# Sheet1.net
KiCad netlist of a schematic drawn in Altium Designer
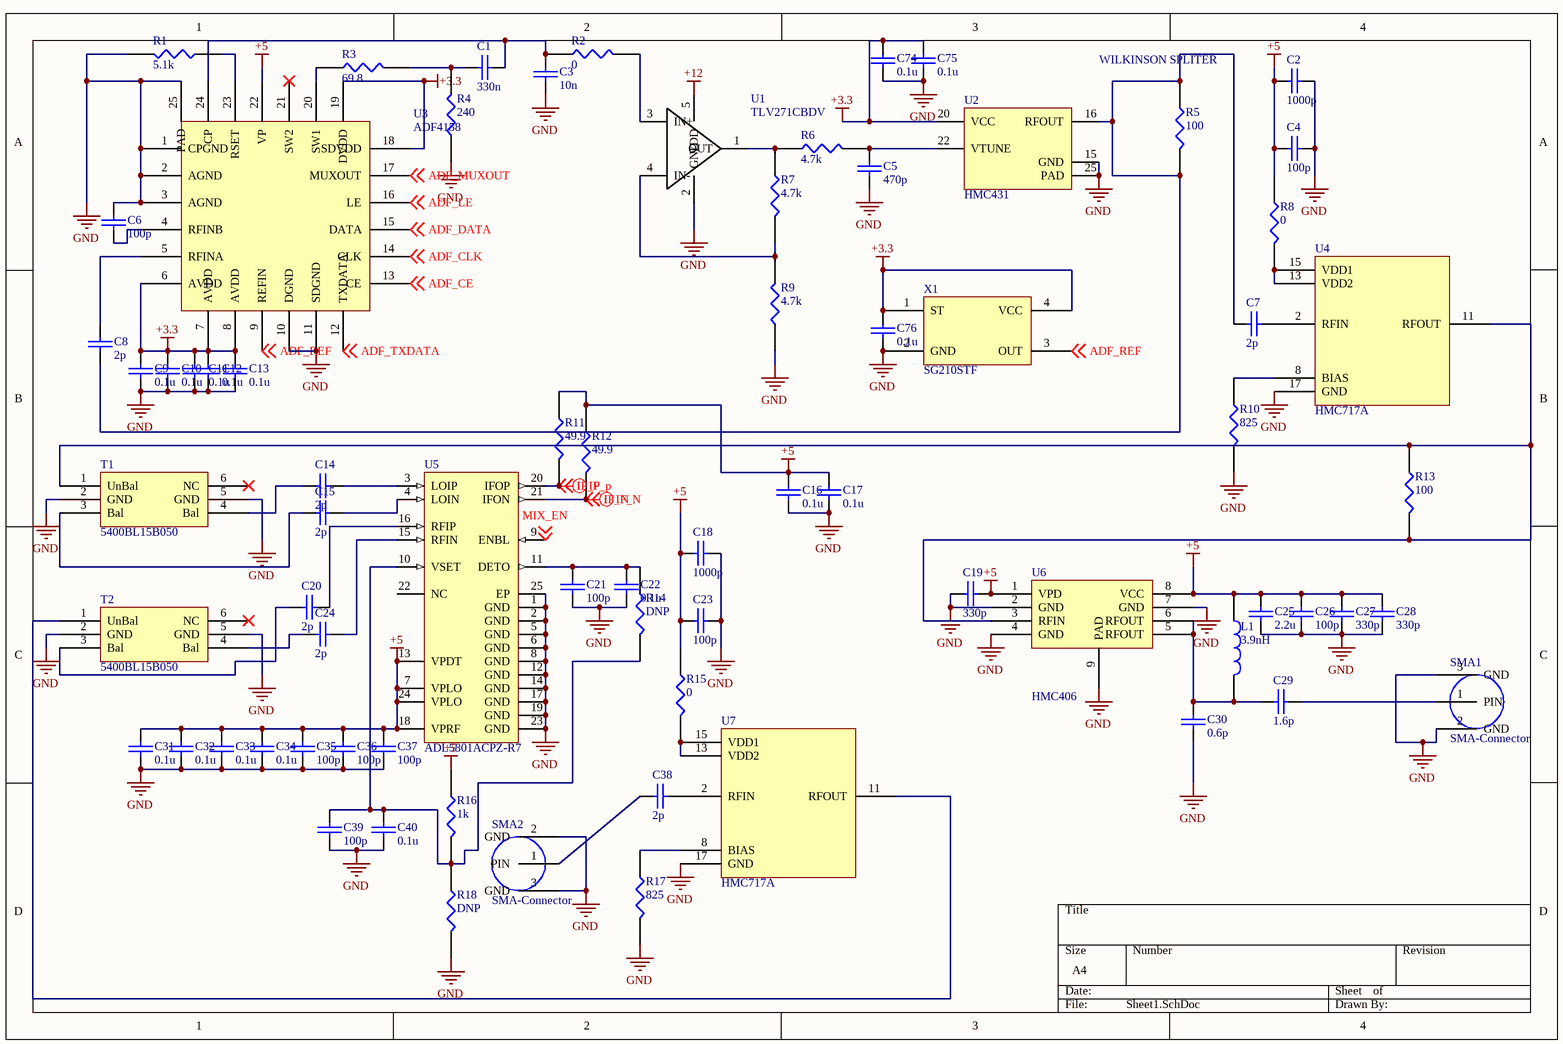
[diagram p0: Sheet1.SchDoc]

(export (version "E")
  (design (tool "Eeschema 10.0.6"))
  (components
    (comp (ref "C1")
      (value "330n")
      (footprint "0603_R")
      (description "Capacitor")
      (libsource (lib "Miscellaneous Devices") (part "CAP"))
    )
    (comp (ref "C2")
      (value "1000p")
      (footprint "0603_R")
      (description "Capacitor")
      (libsource (lib "Miscellaneous Devices") (part "CAP"))
    )
    (comp (ref "C3")
      (value "10n")
      (footprint "0603_R")
      (description "Capacitor")
      (libsource (lib "Miscellaneous Devices") (part "CAP"))
    )
    (comp (ref "C4")
      (value "100p")
      (footprint "0603_R")
      (description "Capacitor")
      (libsource (lib "Miscellaneous Devices") (part "CAP"))
    )
    (comp (ref "C5")
      (value "470p")
      (footprint "0603_R")
      (description "Capacitor")
      (libsource (lib "Miscellaneous Devices") (part "CAP"))
    )
    (comp (ref "C6")
      (value "100p")
      (footprint "0603_R")
      (description "Capacitor")
      (libsource (lib "Miscellaneous Devices") (part "CAP"))
    )
    (comp (ref "C7")
      (value "2p")
      (footprint "0603_R")
      (description "Capacitor")
      (libsource (lib "Miscellaneous Devices") (part "CAP"))
    )
    (comp (ref "C8")
      (value "2p")
      (footprint "0603_R")
      (description "Capacitor")
      (libsource (lib "Miscellaneous Devices") (part "CAP"))
    )
    (comp (ref "C9")
      (value "0.1u")
      (footprint "0603_R")
      (description "Capacitor")
      (libsource (lib "Miscellaneous Devices") (part "CAP"))
    )
    (comp (ref "C10")
      (value "0.1u")
      (footprint "0603_R")
      (description "Capacitor")
      (libsource (lib "Miscellaneous Devices") (part "CAP"))
    )
    (comp (ref "C11")
      (value "0.1u")
      (footprint "0603_R")
      (description "Capacitor")
      (libsource (lib "Miscellaneous Devices") (part "CAP"))
    )
    (comp (ref "C12")
      (value "0.1u")
      (footprint "0603_R")
      (description "Capacitor")
      (libsource (lib "Miscellaneous Devices") (part "CAP"))
    )
    (comp (ref "C13")
      (value "0.1u")
      (footprint "0603_R")
      (description "Capacitor")
      (libsource (lib "Miscellaneous Devices") (part "CAP"))
    )
    (comp (ref "C14")
      (value "2p")
      (footprint "0603_R")
      (description "Capacitor")
      (libsource (lib "Miscellaneous Devices") (part "CAP"))
    )
    (comp (ref "C15")
      (value "2p")
      (footprint "0603_R")
      (description "Capacitor")
      (libsource (lib "Miscellaneous Devices") (part "CAP"))
    )
    (comp (ref "C16")
      (value "0.1u")
      (footprint "0603_R")
      (description "Capacitor")
      (libsource (lib "Miscellaneous Devices") (part "CAP"))
    )
    (comp (ref "C17")
      (value "0.1u")
      (footprint "0603_R")
      (description "Capacitor")
      (libsource (lib "Miscellaneous Devices") (part "CAP"))
    )
    (comp (ref "C18")
      (value "1000p")
      (footprint "0603_R")
      (description "Capacitor")
      (libsource (lib "Miscellaneous Devices") (part "CAP"))
    )
    (comp (ref "C19")
      (value "330p")
      (footprint "0603_R")
      (description "Capacitor")
      (libsource (lib "Miscellaneous Devices") (part "CAP"))
    )
    (comp (ref "C20")
      (value "2p")
      (footprint "0603_R")
      (description "Capacitor")
      (libsource (lib "Miscellaneous Devices") (part "CAP"))
    )
    (comp (ref "C21")
      (value "100p")
      (footprint "0603_R")
      (description "Capacitor")
      (libsource (lib "Miscellaneous Devices") (part "CAP"))
    )
    (comp (ref "C22")
      (value "0.1u")
      (footprint "0603_R")
      (description "Capacitor")
      (libsource (lib "Miscellaneous Devices") (part "CAP"))
    )
    (comp (ref "C23")
      (value "100p")
      (footprint "0603_R")
      (description "Capacitor")
      (libsource (lib "Miscellaneous Devices") (part "CAP"))
    )
    (comp (ref "C24")
      (value "2p")
      (footprint "0603_R")
      (description "Capacitor")
      (libsource (lib "Miscellaneous Devices") (part "CAP"))
    )
    (comp (ref "C25")
      (value "2.2u")
      (footprint "0603_R")
      (description "Capacitor")
      (libsource (lib "Miscellaneous Devices") (part "CAP"))
    )
    (comp (ref "C26")
      (value "100p")
      (footprint "0603_R")
      (description "Capacitor")
      (libsource (lib "Miscellaneous Devices") (part "CAP"))
    )
    (comp (ref "C27")
      (value "330p")
      (footprint "0603_R")
      (description "Capacitor")
      (libsource (lib "Miscellaneous Devices") (part "CAP"))
    )
    (comp (ref "C28")
      (value "330p")
      (footprint "0603_R")
      (description "Capacitor")
      (libsource (lib "Miscellaneous Devices") (part "CAP"))
    )
    (comp (ref "C29")
      (value "1.6p")
      (footprint "0603_R")
      (description "Capacitor")
      (libsource (lib "Miscellaneous Devices") (part "CAP"))
    )
    (comp (ref "C30")
      (value "0.6p")
      (footprint "0603_R")
      (description "Capacitor")
      (libsource (lib "Miscellaneous Devices") (part "CAP"))
    )
    (comp (ref "C31")
      (value "0.1u")
      (footprint "0603_R")
      (description "Capacitor")
      (libsource (lib "Miscellaneous Devices") (part "CAP"))
    )
    (comp (ref "C32")
      (value "0.1u")
      (footprint "0603_R")
      (description "Capacitor")
      (libsource (lib "Miscellaneous Devices") (part "CAP"))
    )
    (comp (ref "C33")
      (value "0.1u")
      (footprint "0603_R")
      (description "Capacitor")
      (libsource (lib "Miscellaneous Devices") (part "CAP"))
    )
    (comp (ref "C34")
      (value "0.1u")
      (footprint "0603_R")
      (description "Capacitor")
      (libsource (lib "Miscellaneous Devices") (part "CAP"))
    )
    (comp (ref "C35")
      (value "100p")
      (footprint "0603_R")
      (description "Capacitor")
      (libsource (lib "Miscellaneous Devices") (part "CAP"))
    )
    (comp (ref "C36")
      (value "100p")
      (footprint "0603_R")
      (description "Capacitor")
      (libsource (lib "Miscellaneous Devices") (part "CAP"))
    )
    (comp (ref "C37")
      (value "100p")
      (footprint "0603_R")
      (description "Capacitor")
      (libsource (lib "Miscellaneous Devices") (part "CAP"))
    )
    (comp (ref "C38")
      (value "2p")
      (footprint "0603_R")
      (description "Capacitor")
      (libsource (lib "Miscellaneous Devices") (part "CAP"))
    )
    (comp (ref "C39")
      (value "100p")
      (footprint "0603_R")
      (description "Capacitor")
      (libsource (lib "Miscellaneous Devices") (part "CAP"))
    )
    (comp (ref "C40")
      (value "0.1u")
      (footprint "0603_R")
      (description "Capacitor")
      (libsource (lib "Miscellaneous Devices") (part "CAP"))
    )
    (comp (ref "C74")
      (value "0.1u")
      (footprint "0603_R")
      (description "Capacitor")
      (libsource (lib "Miscellaneous Devices") (part "CAP"))
    )
    (comp (ref "C75")
      (value "0.1u")
      (footprint "0603_R")
      (description "Capacitor")
      (libsource (lib "Miscellaneous Devices") (part "CAP"))
    )
    (comp (ref "C76")
      (value "0.1u")
      (footprint "0603_R")
      (description "Capacitor")
      (libsource (lib "Miscellaneous Devices") (part "CAP"))
    )
    (comp (ref "L1")
      (value "3.9nH")
      (footprint "0603_R")
      (libsource (lib "Miscellaneous Devices") (part "INDUCTOR"))
    )
    (comp (ref "R1")
      (value "5.1k")
      (footprint "0603_R")
      (libsource (lib "Miscellaneous Devices") (part "RES1"))
    )
    (comp (ref "R2") (value "0") (footprint "0603_R") (libsource (lib "Miscellaneous Devices") (part "RES1")))
    (comp (ref "R3")
      (value "69.8")
      (footprint "0603_R")
      (libsource (lib "Miscellaneous Devices") (part "RES1"))
    )
    (comp (ref "R4")
      (value "240")
      (footprint "0603_R")
      (libsource (lib "Miscellaneous Devices") (part "RES1"))
    )
    (comp (ref "R5")
      (value "100")
      (footprint "0603_R")
      (libsource (lib "Miscellaneous Devices") (part "RES1"))
    )
    (comp (ref "R6")
      (value "4.7k")
      (footprint "0603_R")
      (libsource (lib "Miscellaneous Devices") (part "RES1"))
    )
    (comp (ref "R7")
      (value "4.7k")
      (footprint "0603_R")
      (libsource (lib "Miscellaneous Devices") (part "RES1"))
    )
    (comp (ref "R8") (value "0") (footprint "0603_R") (libsource (lib "Miscellaneous Devices") (part "RES1")))
    (comp (ref "R9")
      (value "4.7k")
      (footprint "0603_R")
      (libsource (lib "Miscellaneous Devices") (part "RES1"))
    )
    (comp (ref "R10")
      (value "825")
      (footprint "0603_R")
      (libsource (lib "Miscellaneous Devices") (part "RES1"))
    )
    (comp (ref "R11")
      (value "49.9")
      (footprint "0603_R")
      (libsource (lib "Miscellaneous Devices") (part "RES1"))
    )
    (comp (ref "R12")
      (value "49.9")
      (footprint "0603_R")
      (libsource (lib "Miscellaneous Devices") (part "RES1"))
    )
    (comp (ref "R13")
      (value "100")
      (footprint "0603_R")
      (libsource (lib "Miscellaneous Devices") (part "RES1"))
    )
    (comp (ref "R14")
      (value "DNP")
      (footprint "0603_R")
      (libsource (lib "Miscellaneous Devices") (part "RES1"))
    )
    (comp (ref "R15")
      (value "0")
      (footprint "0603_R")
      (libsource (lib "Miscellaneous Devices") (part "RES1"))
    )
    (comp (ref "R16")
      (value "1k")
      (footprint "0603_R")
      (libsource (lib "Miscellaneous Devices") (part "RES1"))
    )
    (comp (ref "R17")
      (value "825")
      (footprint "0603_R")
      (libsource (lib "Miscellaneous Devices") (part "RES1"))
    )
    (comp (ref "R18")
      (value "DNP")
      (footprint "0603_R")
      (libsource (lib "Miscellaneous Devices") (part "RES1"))
    )
    (comp (ref "SMA1")
      (value "SMA-Connector")
      (footprint "SMA-2")
      (libsource (lib "SMA") (part "SMA-Connector"))
    )
    (comp (ref "SMA2")
      (value "SMA-Connector")
      (footprint "SMA-2")
      (libsource (lib "SMA") (part "SMA-Connector"))
    )
    (comp (ref "T1")
      (value "5400BL15B050")
      (footprint "0603-6")
      (libsource (lib "Proj") (part "5400BL15B050"))
    )
    (comp (ref "T2")
      (value "5400BL15B050")
      (footprint "0603-6")
      (libsource (lib "Proj") (part "5400BL15B050"))
    )
    (comp (ref "U1")
      (value "TLV271CBDV")
      (footprint "LT-S5-5-TSOT-23_L")
      (libsource (lib "Schlib1") (part "TLV271CBDV"))
    )
    (comp (ref "U2") (value "HMC431") (footprint "LCC24-HMC431") (libsource (lib "Schlib1") (part "HMC431")))
    (comp (ref "U3")
      (value "ADF4158")
      (footprint "LCC24_ADF4158")
      (libsource (lib "Schlib1") (part "ADF4518"))
    )
    (comp (ref "U4") (value "HMC717A") (footprint "LCC16-717A") (libsource (lib "Proj") (part "HMC717A")))
    (comp (ref "U5")
      (value "ADL5801ACPZ-R7")
      (footprint "ADI-CP-24-3_N")
      (description "High IP3, 10 MHz to 6 GHz, Active Mixer, 130mA Supply Current, CP-24-3, Pb-Free, 1500 Reel")
      (libsource (lib "Analog Devices RF IF Mixers and Multipliers") (part "ADL5801ACPZ-R7"))
    )
    (comp (ref "U6") (value "HMC406") (libsource (lib "Proj") (part "HMC406")))
    (comp (ref "U7") (value "HMC717A") (footprint "LCC16-717A") (libsource (lib "Proj") (part "HMC717A")))
    (comp (ref "X1") (value "SG210STF") (footprint "SG210STF") (libsource (lib "Proj") (part "SG210STF")))
  )
  (nets
    (net (code "1") (name "+3.3") (class "Default")
      (node (ref "C10") (pin "1") (pinfunction "1_1") (pintype "passive"))
      (node (ref "C11") (pin "1") (pinfunction "1_1") (pintype "passive"))
      (node (ref "C12") (pin "1") (pinfunction "1_1") (pintype "passive"))
      (node (ref "C13") (pin "1") (pinfunction "1_1") (pintype "passive"))
      (node (ref "C74") (pin "2") (pinfunction "2_2") (pintype "passive"))
      (node (ref "C75") (pin "2") (pinfunction "2_2") (pintype "passive"))
      (node (ref "C76") (pin "1") (pinfunction "1_1") (pintype "passive"))
      (node (ref "C9") (pin "1") (pinfunction "1_1") (pintype "passive"))
      (node (ref "U2") (pin "20") (pinfunction "VCC_20") (pintype "passive"))
      (node (ref "U3") (pin "18") (pinfunction "SDVDD_18") (pintype "passive"))
      (node (ref "U3") (pin "19") (pinfunction "DVDD_19") (pintype "passive"))
      (node (ref "U3") (pin "6") (pinfunction "AVDD_6") (pintype "passive"))
      (node (ref "U3") (pin "7") (pinfunction "AVDD_7") (pintype "passive"))
      (node (ref "U3") (pin "8") (pinfunction "AVDD_8") (pintype "passive"))
      (node (ref "X1") (pin "1") (pinfunction "ST_1") (pintype "passive"))
      (node (ref "X1") (pin "4") (pinfunction "VCC_4") (pintype "passive"))
    )
    (net (code "2") (name "+5") (class "Default")
      (node (ref "C16") (pin "2") (pinfunction "2_2") (pintype "passive"))
      (node (ref "C17") (pin "2") (pinfunction "2_2") (pintype "passive"))
      (node (ref "C18") (pin "1") (pinfunction "1_1") (pintype "passive"))
      (node (ref "C19") (pin "1") (pinfunction "1_1") (pintype "passive"))
      (node (ref "C2") (pin "1") (pinfunction "1_1") (pintype "passive"))
      (node (ref "C23") (pin "1") (pinfunction "1_1") (pintype "passive"))
      (node (ref "C25") (pin "2") (pinfunction "2_2") (pintype "passive"))
      (node (ref "C26") (pin "2") (pinfunction "2_2") (pintype "passive"))
      (node (ref "C27") (pin "2") (pinfunction "2_2") (pintype "passive"))
      (node (ref "C28") (pin "2") (pinfunction "2_2") (pintype "passive"))
      (node (ref "C31") (pin "2") (pinfunction "2_2") (pintype "passive"))
      (node (ref "C32") (pin "2") (pinfunction "2_2") (pintype "passive"))
      (node (ref "C33") (pin "2") (pinfunction "2_2") (pintype "passive"))
      (node (ref "C34") (pin "2") (pinfunction "2_2") (pintype "passive"))
      (node (ref "C35") (pin "2") (pinfunction "2_2") (pintype "passive"))
      (node (ref "C36") (pin "2") (pinfunction "2_2") (pintype "passive"))
      (node (ref "C37") (pin "2") (pinfunction "2_2") (pintype "passive"))
      (node (ref "C4") (pin "1") (pinfunction "1_1") (pintype "passive"))
      (node (ref "L1") (pin "1") (pinfunction "1_1") (pintype "passive"))
      (node (ref "R11") (pin "1") (pinfunction "1_1") (pintype "passive"))
      (node (ref "R12") (pin "1") (pinfunction "1_1") (pintype "passive"))
      (node (ref "R15") (pin "1") (pinfunction "1_1") (pintype "passive"))
      (node (ref "R16") (pin "1") (pinfunction "1_1") (pintype "passive"))
      (node (ref "R8") (pin "1") (pinfunction "1_1") (pintype "passive"))
      (node (ref "U3") (pin "22") (pinfunction "VP_22") (pintype "passive"))
      (node (ref "U5") (pin "13") (pinfunction "VPDT_13") (pintype "power_in"))
      (node (ref "U5") (pin "18") (pinfunction "VPRF_18") (pintype "power_in"))
      (node (ref "U5") (pin "24") (pinfunction "VPLO_24") (pintype "power_in"))
      (node (ref "U5") (pin "7") (pinfunction "VPLO_7") (pintype "power_in"))
      (node (ref "U6") (pin "1") (pinfunction "VPD_1") (pintype "passive"))
      (node (ref "U6") (pin "8") (pinfunction "VCC_8") (pintype "passive"))
    )
    (net (code "3") (name "+12") (class "Default")
      (node (ref "U1") (pin "5") (pinfunction "VDD_5") (pintype "passive"))
    )
    (net (code "4") (name "ADF_CE") (class "Default")
      (node (ref "U3") (pin "13") (pinfunction "CE_13") (pintype "passive"))
    )
    (net (code "5") (name "ADF_CLK") (class "Default")
      (node (ref "U3") (pin "14") (pinfunction "CLK_14") (pintype "passive"))
    )
    (net (code "6") (name "ADF_DATA") (class "Default")
      (node (ref "U3") (pin "15") (pinfunction "DATA_15") (pintype "passive"))
    )
    (net (code "7") (name "ADF_LE") (class "Default")
      (node (ref "U3") (pin "16") (pinfunction "LE_16") (pintype "passive"))
    )
    (net (code "8") (name "ADF_MUXOUT") (class "Default")
      (node (ref "U3") (pin "17") (pinfunction "MUXOUT_17") (pintype "passive"))
    )
    (net (code "9") (name "ADF_REF") (class "Default")
      (node (ref "U3") (pin "9") (pinfunction "REFIN_9") (pintype "passive"))
      (node (ref "X1") (pin "3") (pinfunction "OUT_3") (pintype "passive"))
    )
    (net (code "10") (name "ADF_TXDATA") (class "Default")
      (node (ref "U3") (pin "12") (pinfunction "TXDATA_12") (pintype "passive"))
    )
    (net (code "11") (name "GND") (class "Default")
      (node (ref "C10") (pin "2") (pinfunction "2_2") (pintype "passive"))
      (node (ref "C11") (pin "2") (pinfunction "2_2") (pintype "passive"))
      (node (ref "C12") (pin "2") (pinfunction "2_2") (pintype "passive"))
      (node (ref "C13") (pin "2") (pinfunction "2_2") (pintype "passive"))
      (node (ref "C16") (pin "1") (pinfunction "1_1") (pintype "passive"))
      (node (ref "C17") (pin "1") (pinfunction "1_1") (pintype "passive"))
      (node (ref "C18") (pin "2") (pinfunction "2_2") (pintype "passive"))
      (node (ref "C19") (pin "2") (pinfunction "2_2") (pintype "passive"))
      (node (ref "C2") (pin "2") (pinfunction "2_2") (pintype "passive"))
      (node (ref "C21") (pin "1") (pinfunction "1_1") (pintype "passive"))
      (node (ref "C22") (pin "1") (pinfunction "1_1") (pintype "passive"))
      (node (ref "C23") (pin "2") (pinfunction "2_2") (pintype "passive"))
      (node (ref "C25") (pin "1") (pinfunction "1_1") (pintype "passive"))
      (node (ref "C26") (pin "1") (pinfunction "1_1") (pintype "passive"))
      (node (ref "C27") (pin "1") (pinfunction "1_1") (pintype "passive"))
      (node (ref "C28") (pin "1") (pinfunction "1_1") (pintype "passive"))
      (node (ref "C3") (pin "2") (pinfunction "2_2") (pintype "passive"))
      (node (ref "C30") (pin "1") (pinfunction "1_1") (pintype "passive"))
      (node (ref "C31") (pin "1") (pinfunction "1_1") (pintype "passive"))
      (node (ref "C32") (pin "1") (pinfunction "1_1") (pintype "passive"))
      (node (ref "C33") (pin "1") (pinfunction "1_1") (pintype "passive"))
      (node (ref "C34") (pin "1") (pinfunction "1_1") (pintype "passive"))
      (node (ref "C35") (pin "1") (pinfunction "1_1") (pintype "passive"))
      (node (ref "C36") (pin "1") (pinfunction "1_1") (pintype "passive"))
      (node (ref "C37") (pin "1") (pinfunction "1_1") (pintype "passive"))
      (node (ref "C39") (pin "1") (pinfunction "1_1") (pintype "passive"))
      (node (ref "C4") (pin "2") (pinfunction "2_2") (pintype "passive"))
      (node (ref "C40") (pin "1") (pinfunction "1_1") (pintype "passive"))
      (node (ref "C5") (pin "2") (pinfunction "2_2") (pintype "passive"))
      (node (ref "C6") (pin "1") (pinfunction "1_1") (pintype "passive"))
      (node (ref "C74") (pin "1") (pinfunction "1_1") (pintype "passive"))
      (node (ref "C75") (pin "1") (pinfunction "1_1") (pintype "passive"))
      (node (ref "C76") (pin "2") (pinfunction "2_2") (pintype "passive"))
      (node (ref "C9") (pin "2") (pinfunction "2_2") (pintype "passive"))
      (node (ref "R1") (pin "2") (pinfunction "2_2") (pintype "passive"))
      (node (ref "R10") (pin "2") (pinfunction "2_2") (pintype "passive"))
      (node (ref "R17") (pin "2") (pinfunction "2_2") (pintype "passive"))
      (node (ref "R18") (pin "2") (pinfunction "2_2") (pintype "passive"))
      (node (ref "R4") (pin "1") (pinfunction "1_1") (pintype "passive"))
      (node (ref "R9") (pin "1") (pinfunction "1_1") (pintype "passive"))
      (node (ref "SMA1") (pin "2") (pinfunction "GND_2") (pintype "passive"))
      (node (ref "SMA1") (pin "3") (pinfunction "GND_3") (pintype "passive"))
      (node (ref "SMA2") (pin "2") (pinfunction "GND_2") (pintype "passive"))
      (node (ref "SMA2") (pin "3") (pinfunction "GND_3") (pintype "passive"))
      (node (ref "T1") (pin "2") (pinfunction "GND_2") (pintype "passive"))
      (node (ref "T1") (pin "5") (pinfunction "GND_5") (pintype "passive"))
      (node (ref "T2") (pin "2") (pinfunction "GND_2") (pintype "passive"))
      (node (ref "T2") (pin "5") (pinfunction "GND_5") (pintype "passive"))
      (node (ref "U1") (pin "2") (pinfunction "GND_2") (pintype "passive"))
      (node (ref "U2") (pin "15") (pinfunction "GND_15") (pintype "passive"))
      (node (ref "U2") (pin "25") (pinfunction "PAD_25") (pintype "passive"))
      (node (ref "U3") (pin "1") (pinfunction "CPGND_1") (pintype "passive"))
      (node (ref "U3") (pin "10") (pinfunction "DGND_10") (pintype "passive"))
      (node (ref "U3") (pin "11") (pinfunction "SDGND_11") (pintype "passive"))
      (node (ref "U3") (pin "2") (pinfunction "AGND_2") (pintype "passive"))
      (node (ref "U3") (pin "25") (pinfunction "PAD_25") (pintype "passive"))
      (node (ref "U3") (pin "3") (pinfunction "AGND_3") (pintype "passive"))
      (node (ref "U4") (pin "17") (pinfunction "GND_17") (pintype "passive"))
      (node (ref "U5") (pin "1") (pinfunction "GND_1") (pintype "power_in"))
      (node (ref "U5") (pin "12") (pinfunction "GND_12") (pintype "power_in"))
      (node (ref "U5") (pin "14") (pinfunction "GND_14") (pintype "power_in"))
      (node (ref "U5") (pin "17") (pinfunction "GND_17") (pintype "power_in"))
      (node (ref "U5") (pin "19") (pinfunction "GND_19") (pintype "power_in"))
      (node (ref "U5") (pin "2") (pinfunction "GND_2") (pintype "power_in"))
      (node (ref "U5") (pin "23") (pinfunction "GND_23") (pintype "power_in"))
      (node (ref "U5") (pin "25") (pinfunction "EP_25") (pintype "power_in"))
      (node (ref "U5") (pin "5") (pinfunction "GND_5") (pintype "power_in"))
      (node (ref "U5") (pin "6") (pinfunction "GND_6") (pintype "power_in"))
      (node (ref "U5") (pin "8") (pinfunction "GND_8") (pintype "power_in"))
      (node (ref "U6") (pin "2") (pinfunction "GND_2") (pintype "passive"))
      (node (ref "U6") (pin "4") (pinfunction "GND_4") (pintype "passive"))
      (node (ref "U6") (pin "7") (pinfunction "GND_7") (pintype "passive"))
      (node (ref "U6") (pin "9") (pinfunction "PAD_9") (pintype "passive"))
      (node (ref "U7") (pin "17") (pinfunction "GND_17") (pintype "passive"))
      (node (ref "X1") (pin "2") (pinfunction "GND_2") (pintype "passive"))
    )
    (net (code "12") (name "IF_N") (class "Default")
      (node (ref "R12") (pin "2") (pinfunction "2_2") (pintype "passive"))
      (node (ref "U5") (pin "21") (pinfunction "IFON_21") (pintype "output"))
    )
    (net (code "13") (name "IF_P") (class "Default")
      (node (ref "R11") (pin "2") (pinfunction "2_2") (pintype "passive"))
      (node (ref "U5") (pin "20") (pinfunction "IFOP_20") (pintype "output"))
    )
    (net (code "14") (name "MIX_EN") (class "Default")
      (node (ref "U5") (pin "9") (pinfunction "ENBL_9") (pintype "input"))
    )
    (net (code "15") (name "Net-(C1-Pad1)") (class "Default")
      (node (ref "C1") (pin "1") (pinfunction "1_1") (pintype "passive"))
      (node (ref "R3") (pin "2") (pinfunction "2_2") (pintype "passive"))
      (node (ref "R4") (pin "2") (pinfunction "2_2") (pintype "passive"))
    )
    (net (code "16") (name "Net-(C14-Pad1)") (class "Default")
      (node (ref "C14") (pin "1") (pinfunction "1_1") (pintype "passive"))
      (node (ref "T1") (pin "4") (pinfunction "Bal_4") (pintype "passive"))
    )
    (net (code "17") (name "Net-(C15-Pad1)") (class "Default")
      (node (ref "C15") (pin "1") (pinfunction "1_1") (pintype "passive"))
      (node (ref "T1") (pin "3") (pinfunction "Bal_3") (pintype "passive"))
    )
    (net (code "18") (name "Net-(C20-Pad1)") (class "Default")
      (node (ref "C20") (pin "1") (pinfunction "1_1") (pintype "passive"))
      (node (ref "T2") (pin "3") (pinfunction "Bal_3") (pintype "passive"))
    )
    (net (code "19") (name "Net-(C24-Pad1)") (class "Default")
      (node (ref "C24") (pin "1") (pinfunction "1_1") (pintype "passive"))
      (node (ref "T2") (pin "4") (pinfunction "Bal_4") (pintype "passive"))
    )
    (net (code "20") (name "Net-(C29-Pad2)") (class "Default")
      (node (ref "C29") (pin "2") (pinfunction "2_2") (pintype "passive"))
      (node (ref "C30") (pin "2") (pinfunction "2_2") (pintype "passive"))
      (node (ref "L1") (pin "2") (pinfunction "2_2") (pintype "passive"))
      (node (ref "U6") (pin "5") (pinfunction "RFOUT_5") (pintype "passive"))
      (node (ref "U6") (pin "6") (pinfunction "RFOUT_6") (pintype "passive"))
    )
    (net (code "21") (name "Net-(SMA1-PIN)") (class "Default")
      (node (ref "C29") (pin "1") (pinfunction "1_1") (pintype "passive"))
      (node (ref "SMA1") (pin "1") (pinfunction "PIN_1") (pintype "passive"))
    )
    (net (code "22") (name "Net-(SMA2-PIN)") (class "Default")
      (node (ref "C38") (pin "1") (pinfunction "1_1") (pintype "passive"))
      (node (ref "SMA2") (pin "1") (pinfunction "PIN_1") (pintype "passive"))
    )
    (net (code "23") (name "Net-(T1-UnBal)") (class "Default")
      (node (ref "R13") (pin "1") (pinfunction "1_1") (pintype "passive"))
      (node (ref "R13") (pin "2") (pinfunction "2_2") (pintype "passive"))
      (node (ref "T1") (pin "1") (pinfunction "UnBal_1") (pintype "passive"))
      (node (ref "U4") (pin "11") (pinfunction "RFOUT_11") (pintype "passive"))
      (node (ref "U6") (pin "3") (pinfunction "RFIN_3") (pintype "passive"))
    )
    (net (code "24") (name "Net-(T2-UnBal)") (class "Default")
      (node (ref "T2") (pin "1") (pinfunction "UnBal_1") (pintype "passive"))
      (node (ref "U7") (pin "11") (pinfunction "RFOUT_11") (pintype "passive"))
    )
    (net (code "25") (name "Net-(U1-IN+)") (class "Default")
      (node (ref "R2") (pin "2") (pinfunction "2_2") (pintype "passive"))
      (node (ref "U1") (pin "3") (pinfunction "IN+_3") (pintype "passive"))
    )
    (net (code "26") (name "Net-(U1-IN-)") (class "Default")
      (node (ref "R7") (pin "2") (pinfunction "2_2") (pintype "passive"))
      (node (ref "R9") (pin "2") (pinfunction "2_2") (pintype "passive"))
      (node (ref "U1") (pin "4") (pinfunction "IN-_4") (pintype "passive"))
    )
    (net (code "27") (name "Net-(U1-OUT)") (class "Default")
      (node (ref "R6") (pin "1") (pinfunction "1_1") (pintype "passive"))
      (node (ref "R7") (pin "1") (pinfunction "1_1") (pintype "passive"))
      (node (ref "U1") (pin "1") (pinfunction "OUT_1") (pintype "passive"))
    )
    (net (code "28") (name "Net-(U2-RFOUT)") (class "Default")
      (node (ref "C7") (pin "1") (pinfunction "1_1") (pintype "passive"))
      (node (ref "C8") (pin "2") (pinfunction "2_2") (pintype "passive"))
      (node (ref "R5") (pin "1") (pinfunction "1_1") (pintype "passive"))
      (node (ref "R5") (pin "2") (pinfunction "2_2") (pintype "passive"))
      (node (ref "U2") (pin "16") (pinfunction "RFOUT_16") (pintype "passive"))
    )
    (net (code "29") (name "Net-(U2-VTUNE)") (class "Default")
      (node (ref "C5") (pin "1") (pinfunction "1_1") (pintype "passive"))
      (node (ref "R6") (pin "2") (pinfunction "2_2") (pintype "passive"))
      (node (ref "U2") (pin "22") (pinfunction "VTUNE_22") (pintype "passive"))
    )
    (net (code "30") (name "Net-(U3-CP)") (class "Default")
      (node (ref "C1") (pin "2") (pinfunction "2_2") (pintype "passive"))
      (node (ref "C3") (pin "1") (pinfunction "1_1") (pintype "passive"))
      (node (ref "R2") (pin "1") (pinfunction "1_1") (pintype "passive"))
      (node (ref "U3") (pin "24") (pinfunction "CP_24") (pintype "passive"))
    )
    (net (code "31") (name "Net-(U3-RFINA)") (class "Default")
      (node (ref "C8") (pin "1") (pinfunction "1_1") (pintype "passive"))
      (node (ref "U3") (pin "5") (pinfunction "RFINA_5") (pintype "passive"))
    )
    (net (code "32") (name "Net-(U3-RFINB)") (class "Default")
      (node (ref "C6") (pin "2") (pinfunction "2_2") (pintype "passive"))
      (node (ref "U3") (pin "4") (pinfunction "RFINB_4") (pintype "passive"))
    )
    (net (code "33") (name "Net-(U3-RSET)") (class "Default")
      (node (ref "R1") (pin "1") (pinfunction "1_1") (pintype "passive"))
      (node (ref "U3") (pin "23") (pinfunction "RSET_23") (pintype "passive"))
    )
    (net (code "34") (name "Net-(U3-SW1)") (class "Default")
      (node (ref "R3") (pin "1") (pinfunction "1_1") (pintype "passive"))
      (node (ref "U3") (pin "20") (pinfunction "SW1_20") (pintype "passive"))
    )
    (net (code "35") (name "Net-(U4-BIAS)") (class "Default")
      (node (ref "R10") (pin "1") (pinfunction "1_1") (pintype "passive"))
      (node (ref "U4") (pin "8") (pinfunction "BIAS_8") (pintype "passive"))
    )
    (net (code "36") (name "Net-(U4-RFIN)") (class "Default")
      (node (ref "C7") (pin "2") (pinfunction "2_2") (pintype "passive"))
      (node (ref "U4") (pin "2") (pinfunction "RFIN_2") (pintype "passive"))
    )
    (net (code "37") (name "Net-(U4-VDD1)") (class "Default")
      (node (ref "R8") (pin "2") (pinfunction "2_2") (pintype "passive"))
      (node (ref "U4") (pin "13") (pinfunction "VDD2_13") (pintype "passive"))
      (node (ref "U4") (pin "15") (pinfunction "VDD1_15") (pintype "passive"))
    )
    (net (code "38") (name "Net-(U5-DETO)") (class "Default")
      (node (ref "C21") (pin "2") (pinfunction "2_2") (pintype "passive"))
      (node (ref "C22") (pin "2") (pinfunction "2_2") (pintype "passive"))
      (node (ref "R14") (pin "1") (pinfunction "1_1") (pintype "passive"))
      (node (ref "U5") (pin "11") (pinfunction "DETO_11") (pintype "output"))
    )
    (net (code "39") (name "Net-(U5-LOIN)") (class "Default")
      (node (ref "C15") (pin "2") (pinfunction "2_2") (pintype "passive"))
      (node (ref "U5") (pin "4") (pinfunction "LOIN_4") (pintype "input"))
    )
    (net (code "40") (name "Net-(U5-LOIP)") (class "Default")
      (node (ref "C14") (pin "2") (pinfunction "2_2") (pintype "passive"))
      (node (ref "U5") (pin "3") (pinfunction "LOIP_3") (pintype "input"))
    )
    (net (code "41") (name "Net-(U5-RFIN)") (class "Default")
      (node (ref "C24") (pin "2") (pinfunction "2_2") (pintype "passive"))
      (node (ref "U5") (pin "15") (pinfunction "RFIN_15") (pintype "input"))
    )
    (net (code "42") (name "Net-(U5-RFIP)") (class "Default")
      (node (ref "C20") (pin "2") (pinfunction "2_2") (pintype "passive"))
      (node (ref "U5") (pin "16") (pinfunction "RFIP_16") (pintype "input"))
    )
    (net (code "43") (name "Net-(U5-VSET)") (class "Default")
      (node (ref "C39") (pin "2") (pinfunction "2_2") (pintype "passive"))
      (node (ref "C40") (pin "2") (pinfunction "2_2") (pintype "passive"))
      (node (ref "R14") (pin "2") (pinfunction "2_2") (pintype "passive"))
      (node (ref "R16") (pin "2") (pinfunction "2_2") (pintype "passive"))
      (node (ref "R18") (pin "1") (pinfunction "1_1") (pintype "passive"))
      (node (ref "U5") (pin "10") (pinfunction "VSET_10") (pintype "input"))
    )
    (net (code "44") (name "Net-(U7-BIAS)") (class "Default")
      (node (ref "R17") (pin "1") (pinfunction "1_1") (pintype "passive"))
      (node (ref "U7") (pin "8") (pinfunction "BIAS_8") (pintype "passive"))
    )
    (net (code "45") (name "Net-(U7-RFIN)") (class "Default")
      (node (ref "C38") (pin "2") (pinfunction "2_2") (pintype "passive"))
      (node (ref "U7") (pin "2") (pinfunction "RFIN_2") (pintype "passive"))
    )
    (net (code "46") (name "Net-(U7-VDD1)") (class "Default")
      (node (ref "R15") (pin "2") (pinfunction "2_2") (pintype "passive"))
      (node (ref "U7") (pin "13") (pinfunction "VDD2_13") (pintype "passive"))
      (node (ref "U7") (pin "15") (pinfunction "VDD1_15") (pintype "passive"))
    )
    (net (code "47") (name "unconnected-(T1-NC-Pad6)") (class "Default")
      (node (ref "T1") (pin "6") (pinfunction "NC_6") (pintype "passive+no_connect"))
    )
    (net (code "48") (name "unconnected-(T2-NC-Pad6)") (class "Default")
      (node (ref "T2") (pin "6") (pinfunction "NC_6") (pintype "passive+no_connect"))
    )
    (net (code "49") (name "unconnected-(U3-SW2-Pad21)") (class "Default")
      (node (ref "U3") (pin "21") (pinfunction "SW2_21") (pintype "passive+no_connect"))
    )
    (net (code "50") (name "unconnected-(U5-NC-Pad22)") (class "Default")
      (node (ref "U5") (pin "22") (pinfunction "NC_22") (pintype "passive"))
    )
  )
)
